# STM32_INC.net
KiCad netlist of a schematic drawn in Altium Designer
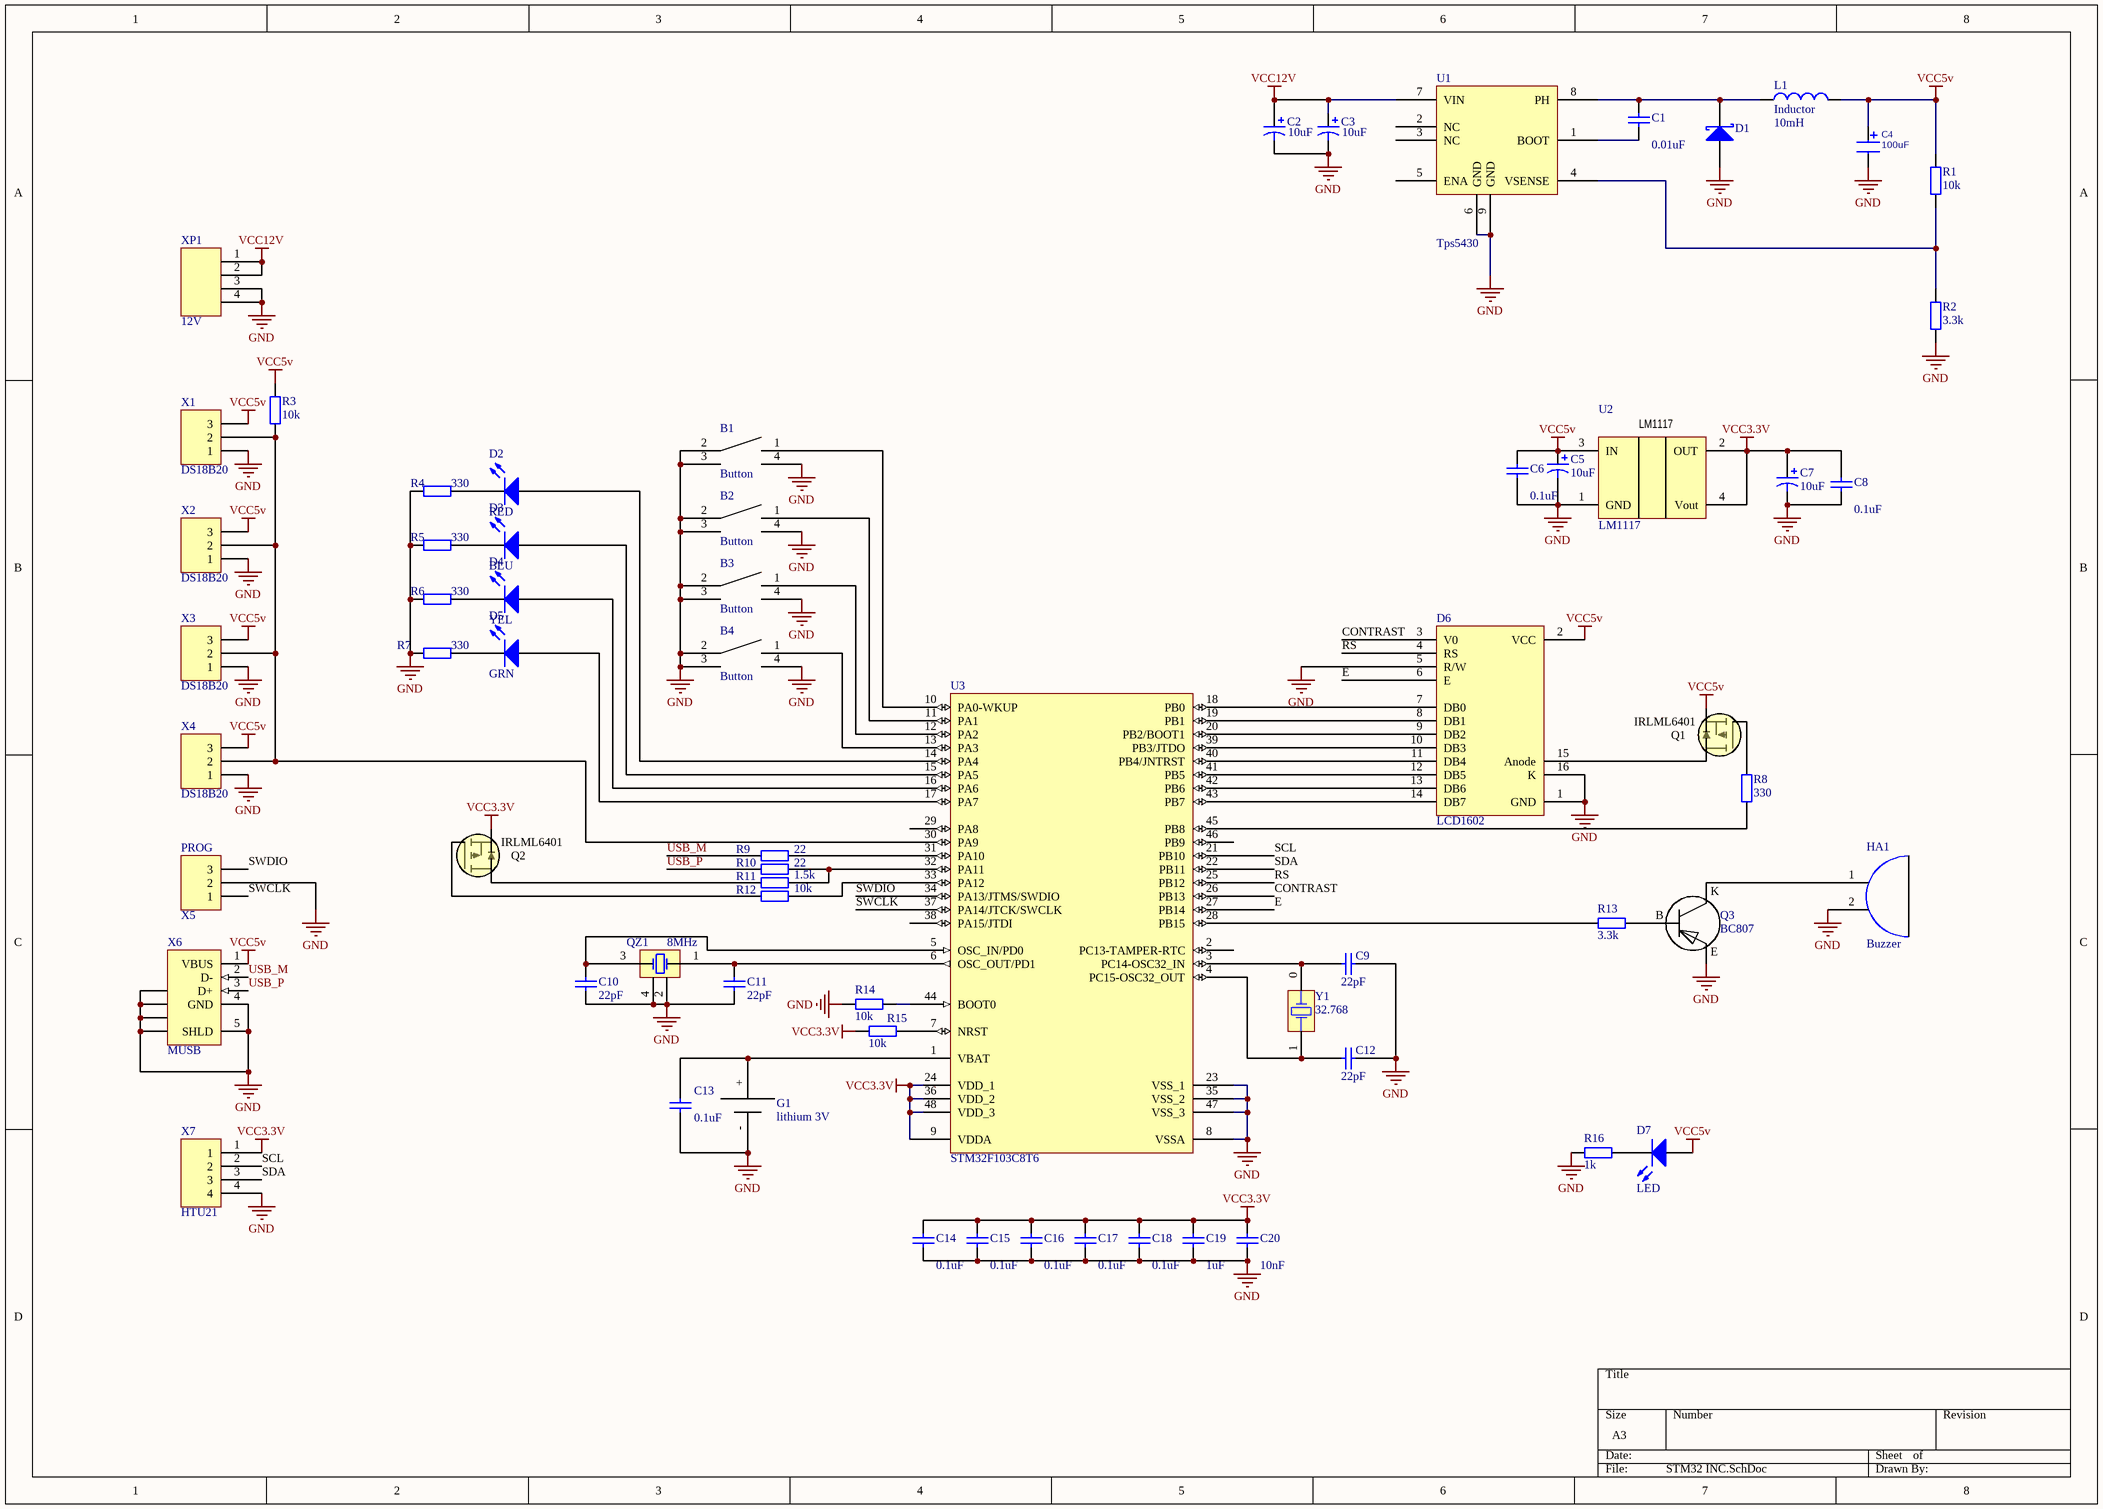
[diagram p0: STM32 INC.SchDoc]

(export (version "E")
  (design (tool "Eeschema 10.0.6"))
  (components
    (comp (ref "B1") (value "Button") (footprint "Button") (libsource (lib "MyLib") (part "Button")))
    (comp (ref "B2") (value "Button") (footprint "Button") (libsource (lib "MyLib") (part "Button")))
    (comp (ref "B3") (value "Button") (footprint "Button") (libsource (lib "MyLib") (part "Button")))
    (comp (ref "B4") (value "Button") (footprint "Button") (libsource (lib "MyLib") (part "Button")))
    (comp (ref "C1")
      (value "0.01uF")
      (footprint "Capacitor 0603")
      (description "Capacitor")
      (libsource (lib "MyLib") (part "Capacitor"))
    )
    (comp (ref "C2")
      (value "10uF")
      (footprint "Capacitor D case")
      (description "Polarized Capacitor (Axial)")
      (fields (field (name "Comment") "Capacitor Polar") (field (name "PUBLISHER") "Altium Limited"))
      (libsource (lib "MyLib") (part "Cap Pol"))
    )
    (comp (ref "C3")
      (value "10uF")
      (footprint "Capacitor D case")
      (description "Polarized Capacitor (Axial)")
      (fields (field (name "Comment") "Capacitor Polar") (field (name "PUBLISHER") "Altium Limited"))
      (libsource (lib "MyLib") (part "Cap Pol"))
    )
    (comp (ref "C4")
      (value "100uF")
      (footprint "Cap 0810")
      (description "Capacitor")
      (libsource (lib "AX_Altium_v2.3") (part "CAP0810Alu"))
    )
    (comp (ref "C5")
      (value "10uF")
      (footprint "Capacitor B case")
      (description "Polarized Capacitor (Axial)")
      (fields (field (name "Comment") "Capacitor Polar") (field (name "PUBLISHER") "Altium Limited"))
      (libsource (lib "MyLib") (part "Cap Pol"))
    )
    (comp (ref "C6")
      (value "0.1uF")
      (footprint "Capacitor 0603")
      (description "Capacitor")
      (libsource (lib "MyLib") (part "Capacitor"))
    )
    (comp (ref "C7")
      (value "10uF")
      (footprint "Capacitor B case")
      (description "Polarized Capacitor (Axial)")
      (fields (field (name "Comment") "Capacitor Polar") (field (name "PUBLISHER") "Altium Limited"))
      (libsource (lib "MyLib") (part "Cap Pol"))
    )
    (comp (ref "C8")
      (value "0.1uF")
      (footprint "Capacitor 0603")
      (description "Capacitor")
      (libsource (lib "MyLib") (part "Capacitor"))
    )
    (comp (ref "C9")
      (value "22pF")
      (footprint "Capacitor 0603")
      (description "Capacitor")
      (libsource (lib "MyLib") (part "Capacitor"))
    )
    (comp (ref "C10")
      (value "22pF")
      (footprint "Capacitor 0603")
      (description "Capacitor")
      (libsource (lib "MyCustomLib") (part "Capacitor"))
    )
    (comp (ref "C11")
      (value "22pF")
      (footprint "Capacitor 0603")
      (description "Capacitor")
      (libsource (lib "MyCustomLib") (part "Capacitor"))
    )
    (comp (ref "C12")
      (value "22pF")
      (footprint "Capacitor 0603")
      (description "Capacitor")
      (libsource (lib "MyLib") (part "Capacitor"))
    )
    (comp (ref "C13")
      (value "0.1uF")
      (footprint "Capacitor 0603")
      (description "Capacitor")
      (libsource (lib "MyLib") (part "Capacitor"))
    )
    (comp (ref "C14")
      (value "0.1uF")
      (footprint "Capacitor 0603")
      (description "Capacitor")
      (libsource (lib "MyCustomLib") (part "Capacitor"))
    )
    (comp (ref "C15")
      (value "0.1uF")
      (footprint "Capacitor 0603")
      (description "Capacitor")
      (libsource (lib "MyCustomLib") (part "Capacitor"))
    )
    (comp (ref "C16")
      (value "0.1uF")
      (footprint "Capacitor 0603")
      (description "Capacitor")
      (libsource (lib "MyCustomLib") (part "Capacitor"))
    )
    (comp (ref "C17")
      (value "0.1uF")
      (footprint "Capacitor 0603")
      (description "Capacitor")
      (libsource (lib "MyCustomLib") (part "Capacitor"))
    )
    (comp (ref "C18")
      (value "0.1uF")
      (footprint "Capacitor 0603")
      (description "Capacitor")
      (libsource (lib "MyCustomLib") (part "Capacitor"))
    )
    (comp (ref "C19")
      (value "1uF")
      (footprint "Capacitor 0603")
      (description "Capacitor")
      (libsource (lib "MyCustomLib") (part "Capacitor"))
    )
    (comp (ref "C20")
      (value "10nF")
      (footprint "Capacitor 0603")
      (description "Capacitor")
      (libsource (lib "MyCustomLib") (part "Capacitor"))
    )
    (comp (ref "D1")
      (value "Diode schottky")
      (footprint "SMC")
      (description "Schottky Rectifier")
      (fields (field (name "PUBLISHER") "Altium Limited"))
      (libsource (lib "MyLib") (part "Diode schottky"))
    )
    (comp (ref "D2")
      (value "RED")
      (footprint "LED0805 RED")
      (description "Typical INFRARED GaAs LED")
      (fields (field (name "PUBLISHER") "Altium Limited"))
      (libsource (lib "MyLib") (part "LED"))
    )
    (comp (ref "D3")
      (value "BLU")
      (footprint "LEDBLUE 00805")
      (description "Typical INFRARED GaAs LED")
      (fields (field (name "PUBLISHER") "Altium Limited"))
      (libsource (lib "MyLib") (part "LED"))
    )
    (comp (ref "D4")
      (value "YEL")
      (footprint "LED0805 YELLOW")
      (description "Typical INFRARED GaAs LED")
      (fields (field (name "PUBLISHER") "Altium Limited"))
      (libsource (lib "MyLib") (part "LED"))
    )
    (comp (ref "D5")
      (value "GRN")
      (footprint "LED0805 GREEN")
      (description "Typical INFRARED GaAs LED")
      (fields (field (name "PUBLISHER") "Altium Limited"))
      (libsource (lib "MyLib") (part "LED"))
    )
    (comp (ref "D6") (value "LCD1602") (footprint "LCD1602") (libsource (lib "MyLib") (part "LCD1602")))
    (comp (ref "D7")
      (value "LED")
      (footprint "LED0805 GREEN")
      (description "Typical INFRARED GaAs LED")
      (fields (field (name "PUBLISHER") "Altium Limited"))
      (libsource (lib "MyCustomLib") (part "LED"))
    )
    (comp (ref "G1")
      (value "lithium 3V")
      (footprint "Battery li-ion CR2032")
      (libsource (lib "MyLib") (part "lithium 3V"))
    )
    (comp (ref "HA1") (value "Buzzer") (footprint "Buzzer") (libsource (lib "MyLib") (part "Buzzer")))
    (comp (ref "L1")
      (value "Inductor")
      (footprint "B82477")
      (fields (field (name "ALTIUM_VALUE") "10mH") (field (name "PUBLISHER") "Altium Limited"))
      (libsource (lib "MyLib") (part "Inductor"))
    )
    (comp (ref "Q1")
      (value "IRLML6401")
      (footprint "SOT23-3_3,0x1,6x0,95")
      (description "P-MOSFET")
      (libsource (lib "ADLibrary") (part "IRLML6401TRPBF"))
    )
    (comp (ref "Q2")
      (value "IRLML6401")
      (footprint "SOT23-3_3,0x1,6x0,95")
      (description "P-MOSFET")
      (libsource (lib "ADLibrary") (part "IRLML6401TRPBF"))
    )
    (comp (ref "Q3") (value "BC807") (footprint "SOT-23") (libsource (lib "MyLib") (part "BC807")))
    (comp (ref "QZ1") (value "8MHz") (footprint "KX – 9A") (libsource (lib "MyCustomLib") (part "KX-7")))
    (comp (ref "R1")
      (value "10k")
      (footprint "RESistor 0603")
      (fields (field (name "Comment") "Resistor"))
      (libsource (lib "MyCustomLib") (part "Resistor"))
    )
    (comp (ref "R2")
      (value "3.3k")
      (footprint "RESistor 0603")
      (fields (field (name "Comment") "Resistor"))
      (libsource (lib "MyCustomLib") (part "Resistor"))
    )
    (comp (ref "R3")
      (value "10k")
      (footprint "RESistor 0603")
      (fields (field (name "Comment") "Resistor"))
      (libsource (lib "MyCustomLib") (part "Resistor"))
    )
    (comp (ref "R4")
      (value "330")
      (footprint "RESistor 0603")
      (fields (field (name "Comment") "Resistor"))
      (libsource (lib "MyCustomLib") (part "Resistor"))
    )
    (comp (ref "R5")
      (value "330")
      (footprint "RESistor 0603")
      (fields (field (name "Comment") "Resistor"))
      (libsource (lib "MyCustomLib") (part "Resistor"))
    )
    (comp (ref "R6")
      (value "330")
      (footprint "RESistor 0603")
      (fields (field (name "Comment") "Resistor"))
      (libsource (lib "MyCustomLib") (part "Resistor"))
    )
    (comp (ref "R7")
      (value "330")
      (footprint "RESistor 0603")
      (fields (field (name "Comment") "Resistor"))
      (libsource (lib "MyCustomLib") (part "Resistor"))
    )
    (comp (ref "R8")
      (value "330")
      (footprint "RESistor 0603")
      (fields (field (name "Comment") "Resistor"))
      (libsource (lib "") (part "Resistor_1"))
    )
    (comp (ref "R9")
      (value "22")
      (footprint "RESistor 0603")
      (fields (field (name "Comment") "Resistor"))
      (libsource (lib "MyCustomLib") (part "Resistor"))
    )
    (comp (ref "R10")
      (value "22")
      (footprint "RESistor 0603")
      (fields (field (name "Comment") "Resistor"))
      (libsource (lib "MyCustomLib") (part "Resistor"))
    )
    (comp (ref "R11")
      (value "1.5k")
      (footprint "RESistor 0603")
      (fields (field (name "Comment") "Resistor"))
      (libsource (lib "") (part "Resistor_1"))
    )
    (comp (ref "R12")
      (value "10k")
      (footprint "RESistor 0603")
      (fields (field (name "Comment") "Resistor"))
      (libsource (lib "") (part "Resistor_1"))
    )
    (comp (ref "R13")
      (value "3.3k")
      (footprint "RESistor 0603")
      (fields (field (name "Comment") "Resistor"))
      (libsource (lib "") (part "Resistor_1"))
    )
    (comp (ref "R14")
      (value "10k")
      (footprint "RESistor 0603")
      (fields (field (name "Comment") "Resistor"))
      (libsource (lib "") (part "Resistor_1"))
    )
    (comp (ref "R15")
      (value "10k")
      (footprint "RESistor 0603")
      (fields (field (name "Comment") "Resistor"))
      (libsource (lib "") (part "Resistor_1"))
    )
    (comp (ref "R16")
      (value "1k")
      (footprint "RESistor 0603")
      (fields (field (name "Comment") "Resistor"))
      (libsource (lib "") (part "Resistor_1"))
    )
    (comp (ref "U1")
      (value "Tps5430")
      (footprint "PSOP8")
      (description "tps5430")
      (libsource (lib "MyCustomLib") (part "TPS5430"))
    )
    (comp (ref "U2")
      (value "LM1117")
      (footprint "SOT-223")
      (description "Linear regulator")
      (libsource (lib "MyLib") (part "lm1117"))
    )
    (comp (ref "U3")
      (value "STM32F103C8T6")
      (footprint "LQFP48_N")
      (description "STM32 ARM-based 32-bit MCU with 64 Kbytes Flash, 48-pin LQFP, Industrial Temperature")
      (fields (field (name "PUBLISHER") "Altium Limited"))
      (libsource (lib "ST Microcontroller 32-Bit STM32") (part "STM32F103C8T6"))
    )
    (comp (ref "X1")
      (value "DS18B20")
      (footprint "PLS-3-3D")
      (description "Header, 3-Pin")
      (fields (field (name "PUBLISHER") "Altium Limited"))
      (libsource (lib "AX_Altium_v2.3") (part "PLS-3"))
    )
    (comp (ref "X2")
      (value "DS18B20")
      (footprint "PLS-3-3D")
      (description "Header, 3-Pin")
      (fields (field (name "PUBLISHER") "Altium Limited"))
      (libsource (lib "AX_Altium_v2.3") (part "PLS-3"))
    )
    (comp (ref "X3")
      (value "DS18B20")
      (footprint "PLS-3-3D")
      (description "Header, 3-Pin")
      (fields (field (name "PUBLISHER") "Altium Limited"))
      (libsource (lib "AX_Altium_v2.3") (part "PLS-3"))
    )
    (comp (ref "X4")
      (value "DS18B20")
      (footprint "PLS-3-3D")
      (description "Header, 3-Pin")
      (fields (field (name "PUBLISHER") "Altium Limited"))
      (libsource (lib "AX_Altium_v2.3") (part "PLS-3"))
    )
    (comp (ref "X5")
      (value "PROG")
      (footprint "PLS-3-2")
      (description "Header, 3-Pin")
      (fields (field (name "PUBLISHER") "Altium Limited"))
      (libsource (lib "AX_Altium_v2.3") (part "PLS2-3"))
    )
    (comp (ref "X6")
      (value "MUSB")
      (footprint "UX60-MB")
      (description "mini USB")
      (fields (field (name "PUBLISHER") "Altium Limited"))
      (libsource (lib "AX_Altium_v2.3") (part "USB_Mini"))
    )
    (comp (ref "X7")
      (value "HTU21")
      (footprint "Header4_254")
      (libsource (lib "MyLib") (part "Header4_2.54.AMP  5-103673-3"))
    )
    (comp (ref "XP1") (value "12V") (footprint "MF2x4MRA") (libsource (lib "MyLib") (part "MF2x2MRA")))
    (comp (ref "Y1")
      (value "32.768")
      (footprint "x3215")
      (description "Crystal Oscillator")
      (libsource (lib "AX_Altium_v2.3") (part "Y_3215"))
    )
  )
  (nets
    (net (code "1") (name "/CONTRAST") (class "Default")
      (node (ref "D6") (pin "3") (pinfunction "V0_3") (pintype "passive"))
      (node (ref "U3") (pin "26") (pinfunction "PB13_26") (pintype "bidirectional"))
    )
    (net (code "2") (name "/E") (class "Default")
      (node (ref "D6") (pin "6") (pinfunction "E_6") (pintype "passive"))
      (node (ref "U3") (pin "27") (pinfunction "PB14_27") (pintype "bidirectional"))
    )
    (net (code "3") (name "/RS") (class "Default")
      (node (ref "D6") (pin "4") (pinfunction "RS_4") (pintype "passive"))
      (node (ref "U3") (pin "25") (pinfunction "PB12_25") (pintype "bidirectional"))
    )
    (net (code "4") (name "/SCL") (class "Default")
      (node (ref "U3") (pin "21") (pinfunction "PB10_21") (pintype "bidirectional"))
      (node (ref "X7") (pin "2") (pinfunction "2_2") (pintype "passive"))
    )
    (net (code "5") (name "/SDA") (class "Default")
      (node (ref "U3") (pin "22") (pinfunction "PB11_22") (pintype "bidirectional"))
      (node (ref "X7") (pin "3") (pinfunction "3_3") (pintype "passive"))
    )
    (net (code "6") (name "/SWCLK") (class "Default")
      (node (ref "U3") (pin "37") (pinfunction "PA14/JTCK/SWCLK_37") (pintype "bidirectional"))
      (node (ref "X5") (pin "1") (pinfunction "1_1") (pintype "passive"))
    )
    (net (code "7") (name "/SWDIO") (class "Default")
      (node (ref "U3") (pin "34") (pinfunction "PA13/JTMS/SWDIO_34") (pintype "bidirectional"))
      (node (ref "X5") (pin "3") (pinfunction "3_3") (pintype "passive"))
    )
    (net (code "8") (name "/USB_M") (class "Default")
      (node (ref "R9") (pin "2") (pinfunction "2_2") (pintype "passive"))
      (node (ref "X6") (pin "2") (pinfunction "D-_2") (pintype "input"))
    )
    (net (code "9") (name "/USB_P") (class "Default")
      (node (ref "R10") (pin "2") (pinfunction "2_2") (pintype "passive"))
      (node (ref "X6") (pin "3") (pinfunction "D+_3") (pintype "input"))
    )
    (net (code "10") (name "GND") (class "Default")
      (node (ref "B1") (pin "2") (pinfunction "2_2") (pintype "passive"))
      (node (ref "B1") (pin "3") (pinfunction "3_3") (pintype "passive"))
      (node (ref "B1") (pin "4") (pinfunction "4_4") (pintype "passive"))
      (node (ref "B2") (pin "2") (pinfunction "2_2") (pintype "passive"))
      (node (ref "B2") (pin "3") (pinfunction "3_3") (pintype "passive"))
      (node (ref "B2") (pin "4") (pinfunction "4_4") (pintype "passive"))
      (node (ref "B3") (pin "2") (pinfunction "2_2") (pintype "passive"))
      (node (ref "B3") (pin "3") (pinfunction "3_3") (pintype "passive"))
      (node (ref "B3") (pin "4") (pinfunction "4_4") (pintype "passive"))
      (node (ref "B4") (pin "2") (pinfunction "2_2") (pintype "passive"))
      (node (ref "B4") (pin "3") (pinfunction "3_3") (pintype "passive"))
      (node (ref "B4") (pin "4") (pinfunction "4_4") (pintype "passive"))
      (node (ref "C10") (pin "2") (pinfunction "2_2") (pintype "passive"))
      (node (ref "C11") (pin "2") (pinfunction "2_2") (pintype "passive"))
      (node (ref "C12") (pin "1") (pinfunction "1_1") (pintype "passive"))
      (node (ref "C13") (pin "1") (pinfunction "1_1") (pintype "passive"))
      (node (ref "C14") (pin "1") (pinfunction "1_1") (pintype "passive"))
      (node (ref "C15") (pin "1") (pinfunction "1_1") (pintype "passive"))
      (node (ref "C16") (pin "1") (pinfunction "1_1") (pintype "passive"))
      (node (ref "C17") (pin "1") (pinfunction "1_1") (pintype "passive"))
      (node (ref "C18") (pin "1") (pinfunction "1_1") (pintype "passive"))
      (node (ref "C19") (pin "1") (pinfunction "1_1") (pintype "passive"))
      (node (ref "C2") (pin "2") (pinfunction "2_2") (pintype "passive"))
      (node (ref "C20") (pin "1") (pinfunction "1_1") (pintype "passive"))
      (node (ref "C3") (pin "2") (pinfunction "2_2") (pintype "passive"))
      (node (ref "C4") (pin "2") (pinfunction "2_2") (pintype "passive"))
      (node (ref "C5") (pin "2") (pinfunction "2_2") (pintype "passive"))
      (node (ref "C6") (pin "1") (pinfunction "1_1") (pintype "passive"))
      (node (ref "C7") (pin "2") (pinfunction "2_2") (pintype "passive"))
      (node (ref "C8") (pin "1") (pinfunction "1_1") (pintype "passive"))
      (node (ref "C9") (pin "1") (pinfunction "1_1") (pintype "passive"))
      (node (ref "D1") (pin "2") (pinfunction "A_2") (pintype "passive"))
      (node (ref "D6") (pin "1") (pinfunction "GND_1") (pintype "passive"))
      (node (ref "D6") (pin "16") (pinfunction "K_16") (pintype "passive"))
      (node (ref "D6") (pin "5") (pinfunction "R/W_5") (pintype "passive"))
      (node (ref "G1") (pin "-") (pinfunction "GND_-") (pintype "passive"))
      (node (ref "HA1") (pin "2") (pinfunction "18_2") (pintype "passive"))
      (node (ref "Q3") (pin "2") (pinfunction "2_2") (pintype "passive"))
      (node (ref "QZ1") (pin "2") (pinfunction "OSC2_2") (pintype "passive"))
      (node (ref "QZ1") (pin "4") (pinfunction "GND_4") (pintype "passive"))
      (node (ref "R14") (pin "1") (pinfunction "1_1") (pintype "passive"))
      (node (ref "R16") (pin "1") (pinfunction "1_1") (pintype "passive"))
      (node (ref "R2") (pin "1") (pinfunction "1_1") (pintype "passive"))
      (node (ref "R4") (pin "2") (pinfunction "2_2") (pintype "passive"))
      (node (ref "R5") (pin "2") (pinfunction "2_2") (pintype "passive"))
      (node (ref "R6") (pin "2") (pinfunction "2_2") (pintype "passive"))
      (node (ref "R7") (pin "2") (pinfunction "2_2") (pintype "passive"))
      (node (ref "U1") (pin "6") (pinfunction "GND_6") (pintype "passive"))
      (node (ref "U1") (pin "9") (pinfunction "GND_9") (pintype "passive"))
      (node (ref "U2") (pin "1") (pinfunction "GND_1") (pintype "passive"))
      (node (ref "U3") (pin "23") (pinfunction "VSS_1_23") (pintype "power_in"))
      (node (ref "U3") (pin "35") (pinfunction "VSS_2_35") (pintype "power_in"))
      (node (ref "U3") (pin "47") (pinfunction "VSS_3_47") (pintype "power_in"))
      (node (ref "U3") (pin "8") (pinfunction "VSSA_8") (pintype "power_in"))
      (node (ref "X1") (pin "1") (pinfunction "1_1") (pintype "passive"))
      (node (ref "X2") (pin "1") (pinfunction "1_1") (pintype "passive"))
      (node (ref "X3") (pin "1") (pinfunction "1_1") (pintype "passive"))
      (node (ref "X4") (pin "1") (pinfunction "1_1") (pintype "passive"))
      (node (ref "X5") (pin "2") (pinfunction "2_2") (pintype "passive"))
      (node (ref "X6") (pin "4") (pinfunction "GND_4") (pintype "power_in"))
      (node (ref "X6") (pin "5") (pinfunction "SHLD_5") (pintype "passive"))
      (node (ref "X6") (pin "6") (pinfunction "SHLD_6") (pintype "passive"))
      (node (ref "X6") (pin "7") (pinfunction "SHLD_7") (pintype "passive"))
      (node (ref "X6") (pin "8") (pinfunction "SHLD_8") (pintype "passive"))
      (node (ref "X6") (pin "9") (pinfunction "SHLD_9") (pintype "passive"))
      (node (ref "X7") (pin "4") (pinfunction "4_4") (pintype "passive"))
      (node (ref "XP1") (pin "3") (pinfunction "3_3") (pintype "passive"))
      (node (ref "XP1") (pin "4") (pinfunction "4_4") (pintype "passive"))
    )
    (net (code "11") (name "Net-(D1-K)") (class "Default")
      (node (ref "C1") (pin "2") (pinfunction "2_2") (pintype "passive"))
      (node (ref "D1") (pin "1") (pinfunction "K_1") (pintype "passive"))
      (node (ref "L1") (pin "1") (pinfunction "1_1") (pintype "passive"))
      (node (ref "U1") (pin "8") (pinfunction "PH_8") (pintype "passive"))
    )
    (net (code "12") (name "Net-(D2-A)") (class "Default")
      (node (ref "D2") (pin "1") (pinfunction "A_1") (pintype "passive"))
      (node (ref "U3") (pin "14") (pinfunction "PA4_14") (pintype "bidirectional"))
    )
    (net (code "13") (name "Net-(D2-K)") (class "Default")
      (node (ref "D2") (pin "2") (pinfunction "K_2") (pintype "passive"))
      (node (ref "R4") (pin "1") (pinfunction "1_1") (pintype "passive"))
    )
    (net (code "14") (name "Net-(D3-A)") (class "Default")
      (node (ref "D3") (pin "1") (pinfunction "A_1") (pintype "passive"))
      (node (ref "U3") (pin "15") (pinfunction "PA5_15") (pintype "bidirectional"))
    )
    (net (code "15") (name "Net-(D3-K)") (class "Default")
      (node (ref "D3") (pin "2") (pinfunction "K_2") (pintype "passive"))
      (node (ref "R5") (pin "1") (pinfunction "1_1") (pintype "passive"))
    )
    (net (code "16") (name "Net-(D4-A)") (class "Default")
      (node (ref "D4") (pin "1") (pinfunction "A_1") (pintype "passive"))
      (node (ref "U3") (pin "16") (pinfunction "PA6_16") (pintype "bidirectional"))
    )
    (net (code "17") (name "Net-(D4-K)") (class "Default")
      (node (ref "D4") (pin "2") (pinfunction "K_2") (pintype "passive"))
      (node (ref "R6") (pin "1") (pinfunction "1_1") (pintype "passive"))
    )
    (net (code "18") (name "Net-(D5-A)") (class "Default")
      (node (ref "D5") (pin "1") (pinfunction "A_1") (pintype "passive"))
      (node (ref "U3") (pin "17") (pinfunction "PA7_17") (pintype "bidirectional"))
    )
    (net (code "19") (name "Net-(D5-K)") (class "Default")
      (node (ref "D5") (pin "2") (pinfunction "K_2") (pintype "passive"))
      (node (ref "R7") (pin "1") (pinfunction "1_1") (pintype "passive"))
    )
    (net (code "20") (name "Net-(D6-Anode)") (class "Default")
      (node (ref "D6") (pin "15") (pinfunction "Anode_15") (pintype "passive"))
      (node (ref "Q1") (pin "3") (pintype "passive"))
    )
    (net (code "21") (name "Net-(D6-DB0)") (class "Default")
      (node (ref "D6") (pin "7") (pinfunction "DB0_7") (pintype "passive"))
      (node (ref "U3") (pin "18") (pinfunction "PB0_18") (pintype "bidirectional"))
    )
    (net (code "22") (name "Net-(D6-DB1)") (class "Default")
      (node (ref "D6") (pin "8") (pinfunction "DB1_8") (pintype "passive"))
      (node (ref "U3") (pin "19") (pinfunction "PB1_19") (pintype "bidirectional"))
    )
    (net (code "23") (name "Net-(D6-DB2)") (class "Default")
      (node (ref "D6") (pin "9") (pinfunction "DB2_9") (pintype "passive"))
      (node (ref "U3") (pin "20") (pinfunction "PB2/BOOT1_20") (pintype "bidirectional"))
    )
    (net (code "24") (name "Net-(D6-DB3)") (class "Default")
      (node (ref "D6") (pin "10") (pinfunction "DB3_10") (pintype "passive"))
      (node (ref "U3") (pin "39") (pinfunction "PB3/JTDO_39") (pintype "bidirectional"))
    )
    (net (code "25") (name "Net-(D6-DB4)") (class "Default")
      (node (ref "D6") (pin "11") (pinfunction "DB4_11") (pintype "passive"))
      (node (ref "U3") (pin "40") (pinfunction "PB4/JNTRST_40") (pintype "bidirectional"))
    )
    (net (code "26") (name "Net-(D6-DB5)") (class "Default")
      (node (ref "D6") (pin "12") (pinfunction "DB5_12") (pintype "passive"))
      (node (ref "U3") (pin "41") (pinfunction "PB5_41") (pintype "bidirectional"))
    )
    (net (code "27") (name "Net-(D6-DB6)") (class "Default")
      (node (ref "D6") (pin "13") (pinfunction "DB6_13") (pintype "passive"))
      (node (ref "U3") (pin "42") (pinfunction "PB6_42") (pintype "bidirectional"))
    )
    (net (code "28") (name "Net-(D6-DB7)") (class "Default")
      (node (ref "D6") (pin "14") (pinfunction "DB7_14") (pintype "passive"))
      (node (ref "U3") (pin "43") (pinfunction "PB7_43") (pintype "bidirectional"))
    )
    (net (code "29") (name "Net-(D7-K)") (class "Default")
      (node (ref "D7") (pin "2") (pinfunction "K_2") (pintype "passive"))
      (node (ref "R16") (pin "2") (pinfunction "2_2") (pintype "passive"))
    )
    (net (code "30") (name "Net-(G1-VBAT)") (class "Default")
      (node (ref "C13") (pin "2") (pinfunction "2_2") (pintype "passive"))
      (node (ref "G1") (pin "+") (pinfunction "VBAT_+") (pintype "passive"))
      (node (ref "U3") (pin "1") (pinfunction "VBAT_1") (pintype "power_in"))
    )
    (net (code "31") (name "Net-(HA1-17)") (class "Default")
      (node (ref "HA1") (pin "1") (pinfunction "17_1") (pintype "passive"))
      (node (ref "Q3") (pin "3") (pinfunction "3_3") (pintype "passive"))
    )
    (net (code "32") (name "Net-(Q1-Pad1)") (class "Default")
      (node (ref "Q1") (pin "1") (pintype "passive"))
      (node (ref "R8") (pin "1") (pinfunction "1_1") (pintype "passive"))
    )
    (net (code "33") (name "Net-(Q2-Pad1)") (class "Default")
      (node (ref "Q2") (pin "1") (pintype "passive"))
      (node (ref "R12") (pin "1") (pinfunction "1_1") (pintype "passive"))
    )
    (net (code "34") (name "Net-(Q2-Pad3)") (class "Default")
      (node (ref "Q2") (pin "3") (pintype "passive"))
      (node (ref "R11") (pin "1") (pinfunction "1_1") (pintype "passive"))
    )
    (net (code "35") (name "Net-(Q3-Pad1)") (class "Default")
      (node (ref "Q3") (pin "1") (pinfunction "1_1") (pintype "passive"))
      (node (ref "R13") (pin "2") (pinfunction "2_2") (pintype "passive"))
    )
    (net (code "36") (name "Net-(QZ1-OSC1)") (class "Default")
      (node (ref "C11") (pin "1") (pinfunction "1_1") (pintype "passive"))
      (node (ref "QZ1") (pin "1") (pinfunction "OSC1_1") (pintype "passive"))
      (node (ref "U3") (pin "6") (pinfunction "OSC_OUT/PD1_6") (pintype "output"))
    )
    (net (code "37") (name "Net-(U1-BOOT)") (class "Default")
      (node (ref "C1") (pin "1") (pinfunction "1_1") (pintype "passive"))
      (node (ref "U1") (pin "1") (pinfunction "BOOT_1") (pintype "passive"))
    )
    (net (code "38") (name "Net-(U1-VSENSE)") (class "Default")
      (node (ref "R1") (pin "1") (pinfunction "1_1") (pintype "passive"))
      (node (ref "R2") (pin "2") (pinfunction "2_2") (pintype "passive"))
      (node (ref "U1") (pin "4") (pinfunction "VSENSE_4") (pintype "passive"))
    )
    (net (code "39") (name "Net-(U3-BOOT0)") (class "Default")
      (node (ref "R14") (pin "2") (pinfunction "2_2") (pintype "passive"))
      (node (ref "U3") (pin "44") (pinfunction "BOOT0_44") (pintype "input"))
    )
    (net (code "40") (name "Net-(U3-NRST)") (class "Default")
      (node (ref "R15") (pin "2") (pinfunction "2_2") (pintype "passive"))
      (node (ref "U3") (pin "7") (pinfunction "NRST_7") (pintype "bidirectional"))
    )
    (net (code "41") (name "Net-(U3-OSC_IN{slash}PD0)") (class "Default")
      (node (ref "C10") (pin "1") (pinfunction "1_1") (pintype "passive"))
      (node (ref "QZ1") (pin "3") (pinfunction "GND_3") (pintype "passive"))
      (node (ref "U3") (pin "5") (pinfunction "OSC_IN/PD0_5") (pintype "input"))
    )
    (net (code "42") (name "Net-(U3-PA0-WKUP)") (class "Default")
      (node (ref "B1") (pin "1") (pinfunction "1_1") (pintype "passive"))
      (node (ref "U3") (pin "10") (pinfunction "PA0-WKUP_10") (pintype "bidirectional"))
    )
    (net (code "43") (name "Net-(U3-PA1)") (class "Default")
      (node (ref "B2") (pin "1") (pinfunction "1_1") (pintype "passive"))
      (node (ref "U3") (pin "11") (pinfunction "PA1_11") (pintype "bidirectional"))
    )
    (net (code "44") (name "Net-(U3-PA2)") (class "Default")
      (node (ref "B3") (pin "1") (pinfunction "1_1") (pintype "passive"))
      (node (ref "U3") (pin "12") (pinfunction "PA2_12") (pintype "bidirectional"))
    )
    (net (code "45") (name "Net-(U3-PA3)") (class "Default")
      (node (ref "B4") (pin "1") (pinfunction "1_1") (pintype "passive"))
      (node (ref "U3") (pin "13") (pinfunction "PA3_13") (pintype "bidirectional"))
    )
    (net (code "46") (name "Net-(U3-PA9)") (class "Default")
      (node (ref "R3") (pin "1") (pinfunction "1_1") (pintype "passive"))
      (node (ref "U3") (pin "30") (pinfunction "PA9_30") (pintype "bidirectional"))
      (node (ref "X1") (pin "2") (pinfunction "2_2") (pintype "passive"))
      (node (ref "X2") (pin "2") (pinfunction "2_2") (pintype "passive"))
      (node (ref "X3") (pin "2") (pinfunction "2_2") (pintype "passive"))
      (node (ref "X4") (pin "2") (pinfunction "2_2") (pintype "passive"))
    )
    (net (code "47") (name "Net-(U3-PA10)") (class "Default")
      (node (ref "R9") (pin "1") (pinfunction "1_1") (pintype "passive"))
      (node (ref "U3") (pin "31") (pinfunction "PA10_31") (pintype "bidirectional"))
    )
    (net (code "48") (name "Net-(U3-PA11)") (class "Default")
      (node (ref "R10") (pin "1") (pinfunction "1_1") (pintype "passive"))
      (node (ref "R11") (pin "2") (pinfunction "2_2") (pintype "passive"))
      (node (ref "U3") (pin "32") (pinfunction "PA11_32") (pintype "bidirectional"))
    )
    (net (code "49") (name "Net-(U3-PA12)") (class "Default")
      (node (ref "R12") (pin "2") (pinfunction "2_2") (pintype "passive"))
      (node (ref "U3") (pin "33") (pinfunction "PA12_33") (pintype "bidirectional"))
    )
    (net (code "50") (name "Net-(U3-PB8)") (class "Default")
      (node (ref "R8") (pin "2") (pinfunction "2_2") (pintype "passive"))
      (node (ref "U3") (pin "45") (pinfunction "PB8_45") (pintype "bidirectional"))
    )
    (net (code "51") (name "Net-(U3-PB15)") (class "Default")
      (node (ref "R13") (pin "1") (pinfunction "1_1") (pintype "passive"))
      (node (ref "U3") (pin "28") (pinfunction "PB15_28") (pintype "bidirectional"))
    )
    (net (code "52") (name "Net-(U3-PC14-OSC32_IN)") (class "Default")
      (node (ref "C9") (pin "2") (pinfunction "2_2") (pintype "passive"))
      (node (ref "U3") (pin "3") (pinfunction "PC14-OSC32_IN_3") (pintype "bidirectional"))
      (node (ref "Y1") (pin "0") (pinfunction "OSC1_0") (pintype "passive"))
    )
    (net (code "53") (name "Net-(U3-PC15-OSC32_OUT)") (class "Default")
      (node (ref "C12") (pin "2") (pinfunction "2_2") (pintype "passive"))
      (node (ref "U3") (pin "4") (pinfunction "PC15-OSC32_OUT_4") (pintype "bidirectional"))
      (node (ref "Y1") (pin "1") (pinfunction "OSC2_1") (pintype "passive"))
    )
    (net (code "54") (name "VCC3.3V") (class "Default")
      (node (ref "C14") (pin "2") (pinfunction "2_2") (pintype "passive"))
      (node (ref "C15") (pin "2") (pinfunction "2_2") (pintype "passive"))
      (node (ref "C16") (pin "2") (pinfunction "2_2") (pintype "passive"))
      (node (ref "C17") (pin "2") (pinfunction "2_2") (pintype "passive"))
      (node (ref "C18") (pin "2") (pinfunction "2_2") (pintype "passive"))
      (node (ref "C19") (pin "2") (pinfunction "2_2") (pintype "passive"))
      (node (ref "C20") (pin "2") (pinfunction "2_2") (pintype "passive"))
      (node (ref "C7") (pin "1") (pinfunction "1_1") (pintype "passive"))
      (node (ref "C8") (pin "2") (pinfunction "2_2") (pintype "passive"))
      (node (ref "Q2") (pin "2") (pintype "passive"))
      (node (ref "R15") (pin "1") (pinfunction "1_1") (pintype "passive"))
      (node (ref "U2") (pin "2") (pinfunction "OUT_2") (pintype "passive"))
      (node (ref "U2") (pin "4") (pinfunction "Vout_4") (pintype "passive"))
      (node (ref "U3") (pin "24") (pinfunction "VDD_1_24") (pintype "power_in"))
      (node (ref "U3") (pin "36") (pinfunction "VDD_2_36") (pintype "power_in"))
      (node (ref "U3") (pin "48") (pinfunction "VDD_3_48") (pintype "power_in"))
      (node (ref "U3") (pin "9") (pinfunction "VDDA_9") (pintype "power_in"))
      (node (ref "X7") (pin "1") (pinfunction "1_1") (pintype "passive"))
    )
    (net (code "55") (name "VCC5v") (class "Default")
      (node (ref "C4") (pin "1") (pinfunction "1_1") (pintype "passive"))
      (node (ref "C5") (pin "1") (pinfunction "1_1") (pintype "passive"))
      (node (ref "C6") (pin "2") (pinfunction "2_2") (pintype "passive"))
      (node (ref "D6") (pin "2") (pinfunction "VCC_2") (pintype "passive"))
      (node (ref "D7") (pin "1") (pinfunction "A_1") (pintype "passive"))
      (node (ref "L1") (pin "2") (pinfunction "2_2") (pintype "passive"))
      (node (ref "Q1") (pin "2") (pintype "passive"))
      (node (ref "R1") (pin "2") (pinfunction "2_2") (pintype "passive"))
      (node (ref "R3") (pin "2") (pinfunction "2_2") (pintype "passive"))
      (node (ref "U2") (pin "3") (pinfunction "IN_3") (pintype "passive"))
      (node (ref "X1") (pin "3") (pinfunction "3_3") (pintype "passive"))
      (node (ref "X2") (pin "3") (pinfunction "3_3") (pintype "passive"))
      (node (ref "X3") (pin "3") (pinfunction "3_3") (pintype "passive"))
      (node (ref "X4") (pin "3") (pinfunction "3_3") (pintype "passive"))
      (node (ref "X6") (pin "1") (pinfunction "VBUS_1") (pintype "power_in"))
    )
    (net (code "56") (name "VCC12V") (class "Default")
      (node (ref "C2") (pin "1") (pinfunction "1_1") (pintype "passive"))
      (node (ref "C3") (pin "1") (pinfunction "1_1") (pintype "passive"))
      (node (ref "U1") (pin "7") (pinfunction "VIN_7") (pintype "passive"))
      (node (ref "XP1") (pin "1") (pinfunction "1_1") (pintype "passive"))
      (node (ref "XP1") (pin "2") (pinfunction "2_2") (pintype "passive"))
    )
    (net (code "57") (name "unconnected-(U1-ENA-Pad5)") (class "Default")
      (node (ref "U1") (pin "5") (pinfunction "ENA_5") (pintype "passive"))
    )
    (net (code "58") (name "unconnected-(U1-NC-Pad2)") (class "Default")
      (node (ref "U1") (pin "2") (pinfunction "NC_2") (pintype "passive"))
    )
    (net (code "59") (name "unconnected-(U1-NC-Pad3)") (class "Default")
      (node (ref "U1") (pin "3") (pinfunction "NC_3") (pintype "passive"))
    )
    (net (code "60") (name "unconnected-(U3-PA8-Pad29)") (class "Default")
      (node (ref "U3") (pin "29") (pinfunction "PA8_29") (pintype "bidirectional"))
    )
    (net (code "61") (name "unconnected-(U3-PA15{slash}JTDI-Pad38)") (class "Default")
      (node (ref "U3") (pin "38") (pinfunction "PA15/JTDI_38") (pintype "bidirectional"))
    )
    (net (code "62") (name "unconnected-(U3-PB9-Pad46)") (class "Default")
      (node (ref "U3") (pin "46") (pinfunction "PB9_46") (pintype "bidirectional"))
    )
    (net (code "63") (name "unconnected-(U3-PC13-TAMPER-RTC-Pad2)") (class "Default")
      (node (ref "U3") (pin "2") (pinfunction "PC13-TAMPER-RTC_2") (pintype "bidirectional"))
    )
  )
)
